# LB_BIT_o14_BRIGHTLED-v03_rev3.net
KiCad netlist of a schematic drawn in EAGLE
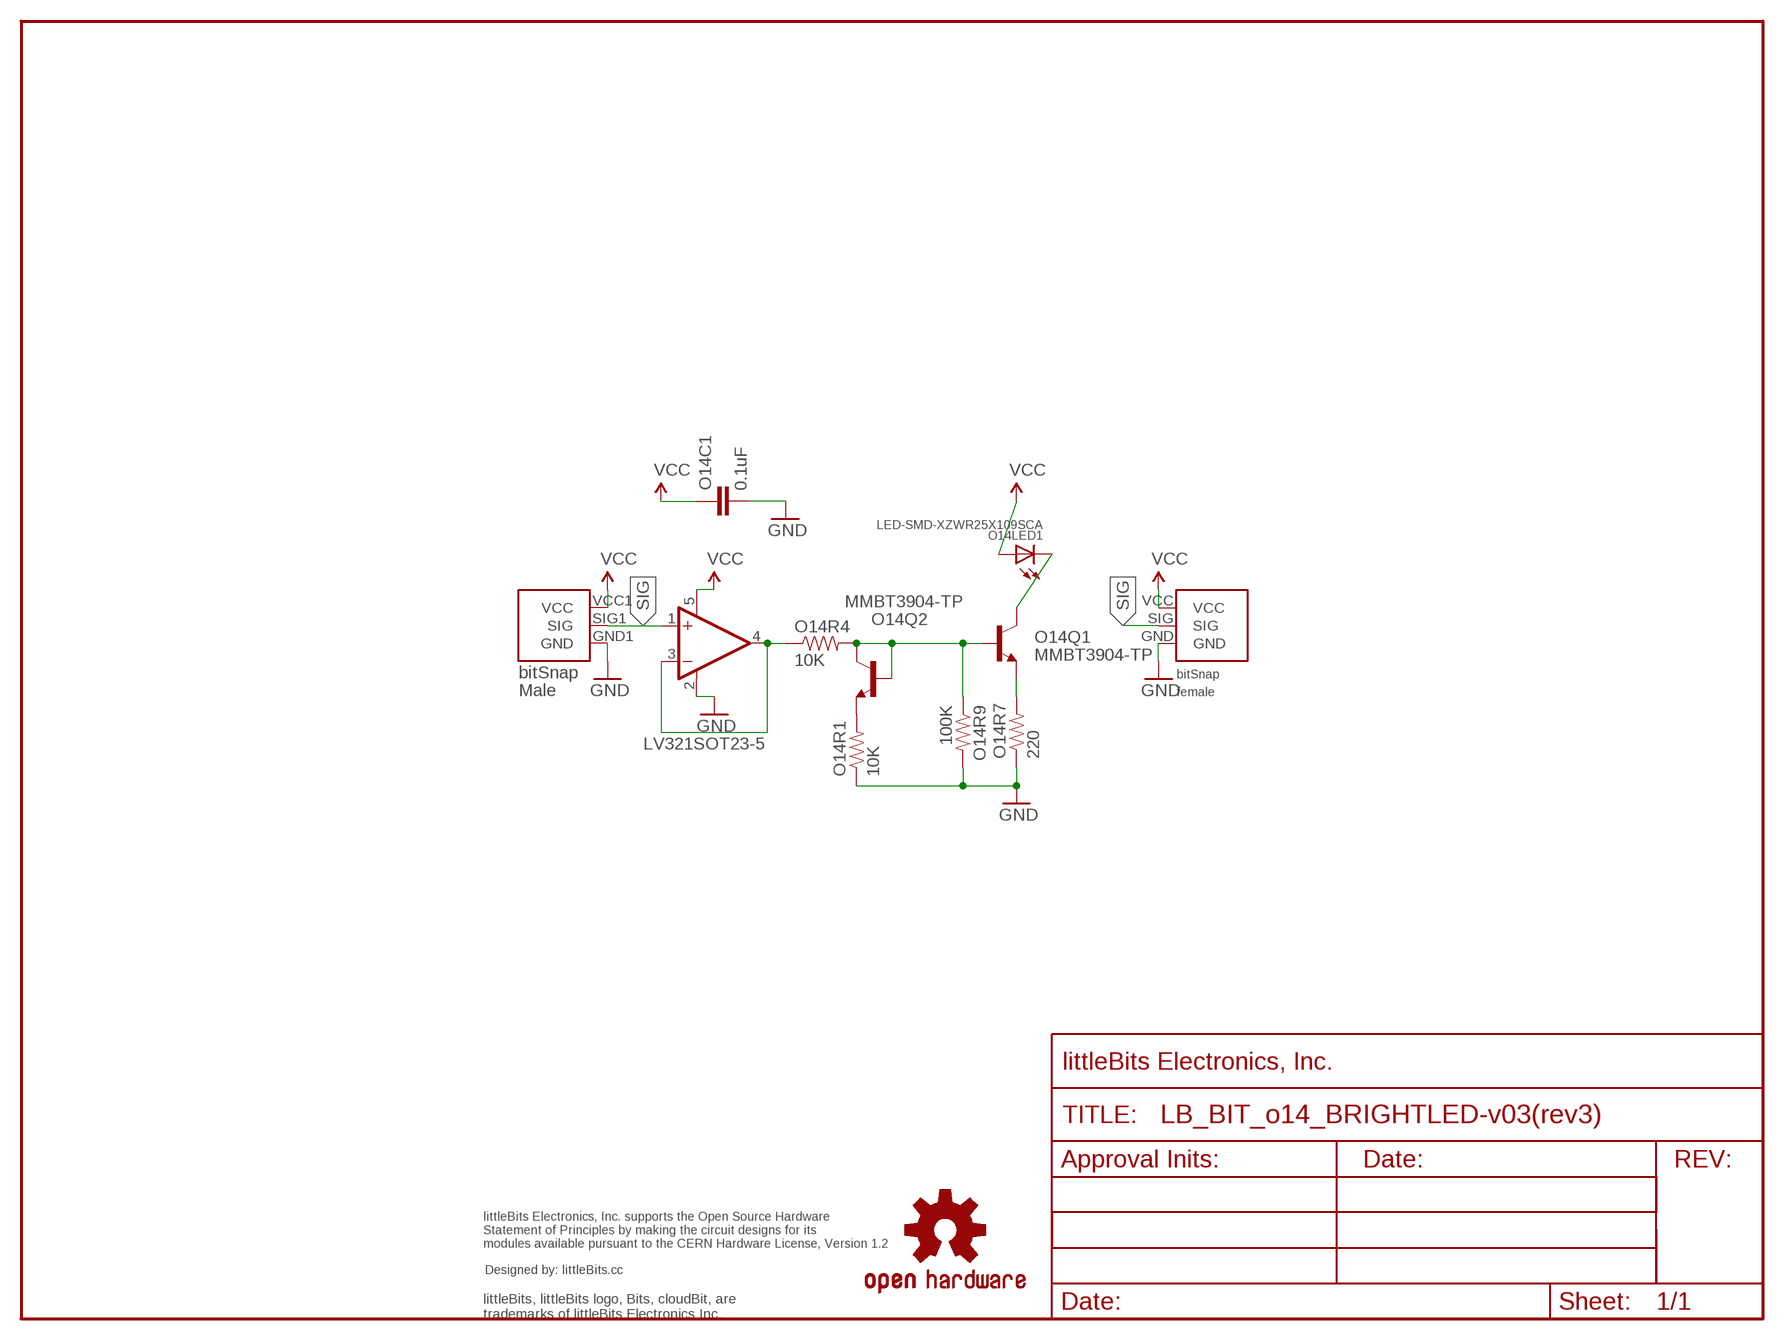
[diagram p0: schematic, sheet 1]

(export (version "E")
  (design (tool "Eeschema 10.0.6"))
  (components
    (comp (ref "O14BSF1")
      (value "BITSNAP_V03_FEMALE")
      (footprint "eagle-import:BITSNAP_V03_FEMALE")
      (libsource (lib "eagle-import") (part "BITSNAP_V03_FEMALE"))
    )
    (comp (ref "O14BSM1")
      (value "BITSNAP_V03_MALE")
      (footprint "eagle-import:BITSNAP_V03_MALE")
      (libsource (lib "eagle-import") (part "BITSNAP_V03_MALE"))
    )
    (comp (ref "O14C1")
      (value "0.1uF")
      (footprint "eagle-import:0603-CAP")
      (libsource (lib "eagle-import") (part "CAP0603-CAP"))
    )
    (comp (ref "O14LED1")
      (value "LED-SMD-XZWR25X109SCA")
      (footprint "eagle-import:LED-SMD-XZWR25X109SCA")
      (libsource (lib "eagle-import") (part "LED-SMD-XZWR25X109SCA"))
    )
    (comp (ref "O14Q1")
      (value "MMBT3904-TP")
      (footprint "eagle-import:SOT23")
      (libsource (lib "eagle-import") (part "TRANSISTOR_NPNSOT23"))
    )
    (comp (ref "O14Q2")
      (value "MMBT3904-TP")
      (footprint "eagle-import:SOT23")
      (libsource (lib "eagle-import") (part "TRANSISTOR_NPNSOT23"))
    )
    (comp (ref "O14R1")
      (value "10K")
      (footprint "eagle-import:0603-RES")
      (libsource (lib "eagle-import") (part "RESISTOR0603-RES"))
    )
    (comp (ref "O14R4")
      (value "10K")
      (footprint "eagle-import:0603-RES")
      (libsource (lib "eagle-import") (part "RESISTOR0603-RES"))
    )
    (comp (ref "O14R7")
      (value "220")
      (footprint "eagle-import:0603-RES")
      (libsource (lib "eagle-import") (part "RESISTOR0603-RES"))
    )
    (comp (ref "O14R9")
      (value "100K")
      (footprint "eagle-import:0603-RES")
      (libsource (lib "eagle-import") (part "RESISTOR0603-RES"))
    )
    (comp (ref "O14U2")
      (value "LV321SOT23-5")
      (footprint "eagle-import:SOT23-5")
      (libsource (lib "eagle-import") (part "LV321SOT23-5"))
    )
    (comp (ref "U$1")
      (value "OSHWCREDIT")
      (footprint "eagle-import:OSHWCREDIT")
      (libsource (lib "eagle-import") (part "OSHWCREDIT"))
    )
    (comp (ref "U$6")
      (value "OSHW-LOGOL")
      (footprint "eagle-import:OSHW-LOGO-L")
      (libsource (lib "eagle-import") (part "OSHW-LOGOL"))
    )
    (comp (ref "U$16")
      (value "FRAME-LETTER-OHWOHW")
      (footprint "eagle-import:FABDWG01-OHW")
      (libsource (lib "eagle-import") (part "FRAME-LETTER-OHWOHW"))
    )
  )
  (nets
    (net (code "1") (name "GND") (class "Default")
      (node (ref "O14BSF1") (pin "GND") (pinfunction "GND_GND") (pintype "bidirectional"))
      (node (ref "O14BSM1") (pin "GND1") (pinfunction "GND_GND1") (pintype "bidirectional"))
      (node (ref "O14C1") (pin "2") (pinfunction "2_2") (pintype "passive"))
      (node (ref "O14R1") (pin "1") (pinfunction "1_1") (pintype "passive"))
      (node (ref "O14R7") (pin "1") (pinfunction "1_1") (pintype "passive"))
      (node (ref "O14R9") (pin "2") (pinfunction "2_2") (pintype "passive"))
      (node (ref "O14U2") (pin "2") (pinfunction "V-_2") (pintype "power_in"))
    )
    (net (code "2") (name "Net-(O14Q1-B)") (class "Default")
      (node (ref "O14Q1") (pin "1") (pinfunction "B_1") (pintype "passive"))
      (node (ref "O14Q2") (pin "1") (pinfunction "B_1") (pintype "passive"))
      (node (ref "O14Q2") (pin "3") (pinfunction "C_3") (pintype "passive"))
      (node (ref "O14R4") (pin "2") (pinfunction "2_2") (pintype "passive"))
      (node (ref "O14R9") (pin "1") (pinfunction "1_1") (pintype "passive"))
    )
    (net (code "3") (name "Net-(O14Q1-C)") (class "Default")
      (node (ref "O14LED1") (pin "C") (pinfunction "C_C") (pintype "passive"))
      (node (ref "O14Q1") (pin "3") (pinfunction "C_3") (pintype "passive"))
    )
    (net (code "4") (name "Net-(O14Q1-E)") (class "Default")
      (node (ref "O14Q1") (pin "2") (pinfunction "E_2") (pintype "passive"))
      (node (ref "O14R7") (pin "2") (pinfunction "2_2") (pintype "passive"))
    )
    (net (code "5") (name "Net-(O14Q2-E)") (class "Default")
      (node (ref "O14Q2") (pin "2") (pinfunction "E_2") (pintype "passive"))
      (node (ref "O14R1") (pin "2") (pinfunction "2_2") (pintype "passive"))
    )
    (net (code "6") (name "Net-(O14U2--IN)") (class "Default")
      (node (ref "O14R4") (pin "1") (pinfunction "1_1") (pintype "passive"))
      (node (ref "O14U2") (pin "3") (pinfunction "-IN_3") (pintype "input"))
      (node (ref "O14U2") (pin "4") (pinfunction "OUT_4") (pintype "output"))
    )
    (net (code "7") (name "SIG") (class "Default")
      (node (ref "O14BSF1") (pin "SIG") (pinfunction "SIG_SIG") (pintype "bidirectional"))
      (node (ref "O14BSM1") (pin "SIG1") (pinfunction "SIG_SIG1") (pintype "bidirectional"))
      (node (ref "O14U2") (pin "1") (pinfunction "+IN_1") (pintype "input"))
    )
    (net (code "8") (name "VCC") (class "Default")
      (node (ref "O14BSF1") (pin "VCC") (pinfunction "VCC_VCC") (pintype "bidirectional"))
      (node (ref "O14BSM1") (pin "VCC1") (pinfunction "VCC_VCC1") (pintype "bidirectional"))
      (node (ref "O14C1") (pin "1") (pinfunction "1_1") (pintype "passive"))
      (node (ref "O14LED1") (pin "A") (pinfunction "A_A") (pintype "passive"))
      (node (ref "O14U2") (pin "5") (pinfunction "V+_5") (pintype "power_in"))
    )
  )
)
